# melody_generator.net
KiCad netlist of a schematic drawn in EAGLE
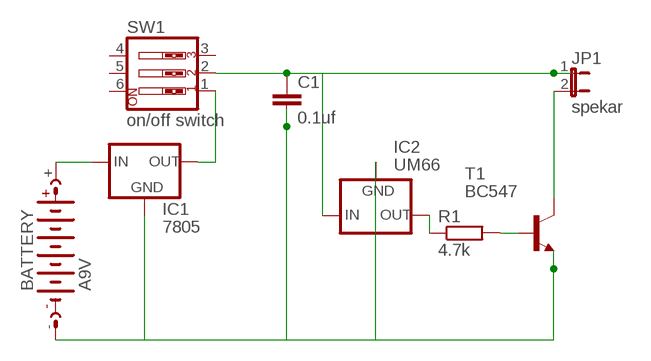
[diagram p0: schematic, sheet 1]

(export (version "E")
  (design (tool "Eeschema 10.0.6"))
  (components
    (comp (ref "BATTERY")
      (value "A9V")
      (footprint "eagle-import:AB9V")
      (libsource (lib "eagle-import") (part "AB9V"))
    )
    (comp (ref "C1")
      (value "0.1uf")
      (footprint "eagle-import:C2.5-2")
      (libsource (lib "eagle-import") (part "C2.5/2"))
    )
    (comp (ref "IC1")
      (value "7805")
      (footprint "eagle-import:78XXL")
      (libsource (lib "eagle-import") (part "78XXL"))
    )
    (comp (ref "IC2")
      (value "UM66")
      (footprint "eagle-import:79LXX")
      (libsource (lib "eagle-import") (part "79LXX"))
    )
    (comp (ref "JP1")
      (value "spekar")
      (footprint "eagle-import:JP1")
      (libsource (lib "eagle-import") (part "JP1E"))
    )
    (comp (ref "R1")
      (value "4.7k")
      (footprint "eagle-import:0204_7")
      (libsource (lib "eagle-import") (part "R-EU_0204/7"))
    )
    (comp (ref "SW1")
      (value "on/off switch")
      (footprint "eagle-import:EDG-03")
      (libsource (lib "eagle-import") (part "SW_DIP-3"))
    )
    (comp (ref "T1")
      (value "BC547")
      (footprint "eagle-import:TO92")
      (libsource (lib "eagle-import") (part "BC547"))
    )
  )
  (nets
    (net (code "1") (name "Net-(BATTERY-Pad+)") (class "Default")
      (node (ref "BATTERY") (pin "+") (pinfunction "+_+") (pintype "passive"))
      (node (ref "IC1") (pin "IN") (pinfunction "IN_IN") (pintype "input"))
    )
    (net (code "2") (name "Net-(C1-Pad1)") (class "Default")
      (node (ref "C1") (pin "1") (pinfunction "1_1") (pintype "passive"))
      (node (ref "IC2") (pin "IN") (pinfunction "IN_IN") (pintype "input"))
      (node (ref "JP1") (pin "1") (pinfunction "1_1") (pintype "passive"))
      (node (ref "SW1") (pin "2") (pinfunction "2_2") (pintype "passive"))
    )
    (net (code "3") (name "Net-(IC1-PadOUT)") (class "Default")
      (node (ref "IC1") (pin "OUT") (pinfunction "OUT_OUT") (pintype "passive"))
      (node (ref "SW1") (pin "1") (pinfunction "1_1") (pintype "passive"))
    )
    (net (code "4") (name "Net-(IC2-PadOUT)") (class "Default")
      (node (ref "IC2") (pin "OUT") (pinfunction "OUT_OUT") (pintype "passive"))
      (node (ref "R1") (pin "1") (pinfunction "1_1") (pintype "passive"))
    )
    (net (code "5") (name "Net-(T1-B)") (class "Default")
      (node (ref "R1") (pin "2") (pinfunction "2_2") (pintype "passive"))
      (node (ref "T1") (pin "2") (pinfunction "B_2") (pintype "passive"))
    )
    (net (code "6") (name "Net-(T1-C)") (class "Default")
      (node (ref "JP1") (pin "2") (pinfunction "2_2") (pintype "passive"))
      (node (ref "T1") (pin "3") (pinfunction "C_3") (pintype "passive"))
    )
    (net (code "7") (name "Net-(T1-E)") (class "Default")
      (node (ref "BATTERY") (pin "-") (pinfunction "-_-") (pintype "passive"))
      (node (ref "C1") (pin "2") (pinfunction "2_2") (pintype "passive"))
      (node (ref "IC1") (pin "GND") (pinfunction "GND_GND") (pintype "input"))
      (node (ref "IC2") (pin "GND") (pinfunction "GND_GND") (pintype "input"))
      (node (ref "T1") (pin "1") (pinfunction "E_1") (pintype "passive"))
    )
    (net (code "8") (name "unconnected-(SW1-Pad3)") (class "Default")
      (node (ref "SW1") (pin "3") (pinfunction "3_3") (pintype "passive"))
    )
    (net (code "9") (name "unconnected-(SW1-Pad4)") (class "Default")
      (node (ref "SW1") (pin "4") (pinfunction "4_4") (pintype "passive"))
    )
    (net (code "10") (name "unconnected-(SW1-Pad5)") (class "Default")
      (node (ref "SW1") (pin "5") (pinfunction "5_5") (pintype "passive"))
    )
    (net (code "11") (name "unconnected-(SW1-Pad6)") (class "Default")
      (node (ref "SW1") (pin "6") (pinfunction "6_6") (pintype "passive"))
    )
  )
)
